# Main.net
KiCad netlist of a schematic drawn in Altium Designer
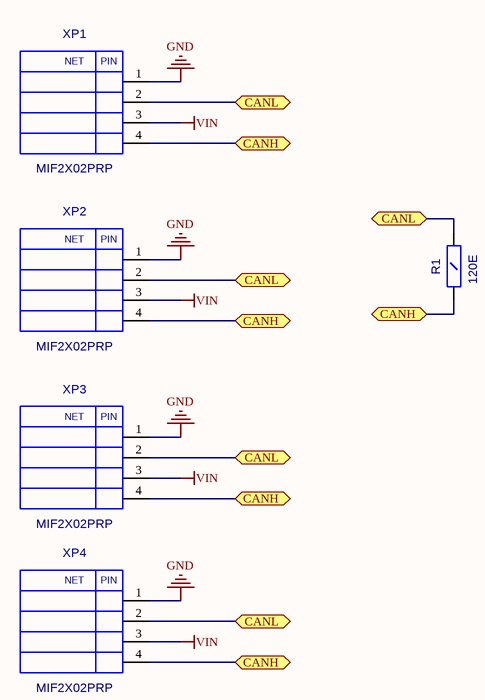
[diagram p0: Main.SchDoc]

(export (version "E")
  (design (tool "Eeschema 10.0.6"))
  (components
    (comp (ref "R1")
      (value "120E")
      (footprint "RC1206")
      (description "RC1206")
      (libsource (lib "gprs_modem_2") (part "RC1206"))
    )
    (comp (ref "XP1")
      (value "MIF2X02PRP")
      (footprint "MIF2X02PRP")
      (libsource (lib "Schetchik") (part "MIF2X02PRP"))
    )
    (comp (ref "XP2")
      (value "MIF2X02PRP")
      (footprint "MIF2X02PRP")
      (libsource (lib "Schetchik") (part "MIF2X02PRP"))
    )
    (comp (ref "XP3")
      (value "MIF2X02PRP")
      (footprint "MIF2X02PRP")
      (libsource (lib "Schetchik") (part "MIF2X02PRP"))
    )
    (comp (ref "XP4")
      (value "MIF2X02PRP")
      (footprint "MIF2X02PRP")
      (libsource (lib "Schetchik") (part "MIF2X02PRP"))
    )
  )
  (nets
    (net (code "1") (name "/CANH") (class "Default")
      (node (ref "R1") (pin "1") (pinfunction "A_1") (pintype "passive"))
      (node (ref "XP1") (pin "4") (pinfunction "4_4") (pintype "passive"))
      (node (ref "XP2") (pin "4") (pinfunction "4_4") (pintype "passive"))
      (node (ref "XP3") (pin "4") (pinfunction "4_4") (pintype "passive"))
      (node (ref "XP4") (pin "4") (pinfunction "4_4") (pintype "passive"))
    )
    (net (code "2") (name "/CANL") (class "Default")
      (node (ref "R1") (pin "2") (pinfunction "B_2") (pintype "passive"))
      (node (ref "XP1") (pin "2") (pinfunction "2_2") (pintype "passive"))
      (node (ref "XP2") (pin "2") (pinfunction "2_2") (pintype "passive"))
      (node (ref "XP3") (pin "2") (pinfunction "2_2") (pintype "passive"))
      (node (ref "XP4") (pin "2") (pinfunction "2_2") (pintype "passive"))
    )
    (net (code "3") (name "GND") (class "Default")
      (node (ref "XP1") (pin "1") (pinfunction "1_1") (pintype "passive"))
      (node (ref "XP2") (pin "1") (pinfunction "1_1") (pintype "passive"))
      (node (ref "XP3") (pin "1") (pinfunction "1_1") (pintype "passive"))
      (node (ref "XP4") (pin "1") (pinfunction "1_1") (pintype "passive"))
    )
    (net (code "4") (name "VIN") (class "Default")
      (node (ref "XP1") (pin "3") (pinfunction "3_3") (pintype "passive"))
      (node (ref "XP2") (pin "3") (pinfunction "3_3") (pintype "passive"))
      (node (ref "XP3") (pin "3") (pinfunction "3_3") (pintype "passive"))
      (node (ref "XP4") (pin "3") (pinfunction "3_3") (pintype "passive"))
    )
  )
)
